# Instrument.net
KiCad netlist of a schematic drawn in Altium Designer
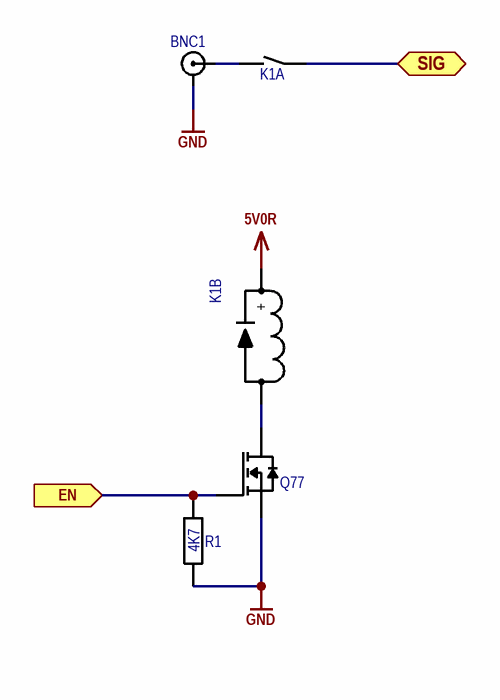
[diagram p0: Instrument.SchDoc]

(export (version "E")
  (design (tool "Eeschema 10.0.6"))
  (components
    (comp (ref "BNC1")
      (value "X")
      (footprint "BNC")
      (description "BNC Connector")
      (fields
        (field (name "07. MANUFACTURER  PART NUMBER") "[see model description]")
        (field (name "13. CREATED DATE/NAME") "AUG 2018 / Hören")
      )
      (libsource (lib "Connectors") (part "BNC"))
    )
    (comp (ref "K1")
      (value "K")
      (footprint "118-1A")
      (description "5V Signal Relais, Normal Open")
      (fields
        (field (name "02. DISTRIBUTOR PART NUMBER") "118-1-A-5/2D")
        (field (name "13. CREATED DATE/NAME") "20.12.17 S. Kaiser")
      )
      (libsource (lib "chickenfood") (part "118-1-A-5/2D"))
    )
    (comp (ref "Q77")
      (value "Q")
      (footprint "SOT23-3")
      (description "MOSFET N-CH 25V 680MA SOT-23")
      (fields
        (field (name "02. DISTRIBUTOR PART NUMBER") "FDV303NDKR-ND")
        (field (name "07. MANUFACTURER  PART NUMBER") "FDV303N")
        (field (name "13. CREATED DATE/NAME") "AUG 2018 / Hören")
      )
      (libsource (lib "SCT8-Board1") (part "FDV303N"))
    )
    (comp (ref "R1")
      (value "4K7")
      (footprint "R0402 Reflow")
      (description "Resistor")
      (fields
        (field (name "TOLERANCE") "±1%")
        (field (name "Comment") "R")
        (field (name "13. CREATED DATE/NAME") "AUG2018/Hören")
      )
      (libsource (lib "chickenfood") (part "R"))
    )
  )
  (nets
    (net (code "1") (name "/EN") (class "Default")
      (node (ref "Q77") (pin "1") (pinfunction "G_1") (pintype "passive"))
      (node (ref "R1") (pin "2") (pinfunction "2_2") (pintype "passive"))
    )
    (net (code "2") (name "/SIG") (class "Default")
      (node (ref "K1") (pin "4") (pinfunction "CB_4") (pintype "passive"))
    )
    (net (code "3") (name "5V0R") (class "Default")
      (node (ref "K1") (pin "1") (pinfunction "+_1") (pintype "passive"))
    )
    (net (code "4") (name "GND") (class "Default")
      (node (ref "BNC1") (pin "0") (pinfunction "0_0") (pintype "passive"))
      (node (ref "Q77") (pin "2") (pinfunction "S_2") (pintype "passive"))
      (node (ref "R1") (pin "1") (pinfunction "1_1") (pintype "passive"))
    )
    (net (code "5") (name "Net-(K1A-CA)") (class "Default")
      (node (ref "BNC1") (pin "1") (pinfunction "1_1") (pintype "passive"))
      (node (ref "K1") (pin "3") (pinfunction "CA_3") (pintype "passive"))
    )
    (net (code "6") (name "Net-(K1B--)") (class "Default")
      (node (ref "K1") (pin "2") (pinfunction "-_2") (pintype "passive"))
      (node (ref "Q77") (pin "3") (pinfunction "D_3") (pintype "passive"))
    )
  )
)
